# Connectors.net
KiCad netlist of a schematic drawn in Altium Designer
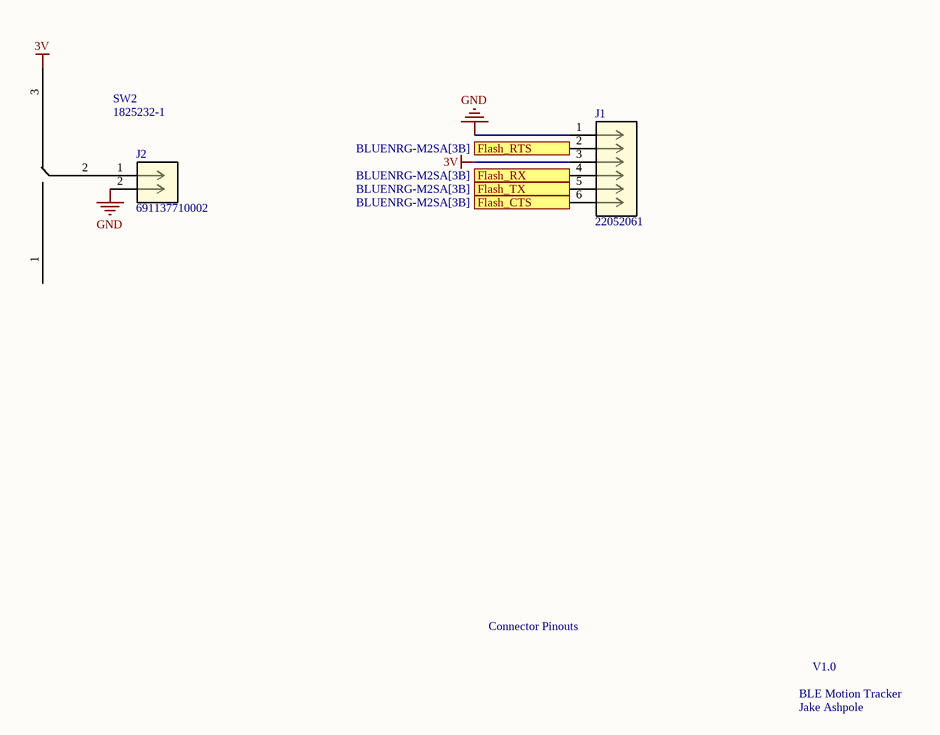
[diagram p0: Connectors.SchDoc]

(export (version "E")
  (design (tool "Eeschema 10.0.6"))
  (components
    (comp (ref "J1")
      (value "22052061")
      (footprint "CONN_22-05-2061_MOL")
      (libsource (lib "22052061") (part "22052061"))
    )
    (comp (ref "J2")
      (value "691137710002")
      (footprint "CONN2_710002_WRE")
      (libsource (lib "691137710002") (part "691137710002"))
    )
    (comp (ref "SW2")
      (value "1825232-1")
      (footprint "1825232-1_TEC")
      (description "https://www.mouser.com/ProductDetail/655-1825232-1")
      (libsource (lib "1825232-1") (part "1825232-1"))
    )
  )
  (nets
    (net (code "1") (name "/Flash_CTS") (class "Default")
      (node (ref "J1") (pin "6") (pinfunction "6_6") (pintype "passive"))
    )
    (net (code "2") (name "/Flash_RTS") (class "Default")
      (node (ref "J1") (pin "2") (pinfunction "2_2") (pintype "passive"))
    )
    (net (code "3") (name "/Flash_RX") (class "Default")
      (node (ref "J1") (pin "4") (pinfunction "4_4") (pintype "passive"))
    )
    (net (code "4") (name "/Flash_TX") (class "Default")
      (node (ref "J1") (pin "5") (pinfunction "5_5") (pintype "passive"))
    )
    (net (code "5") (name "3V") (class "Default")
      (node (ref "J1") (pin "3") (pinfunction "3_3") (pintype "passive"))
      (node (ref "SW2") (pin "3") (pinfunction "3_3") (pintype "passive"))
    )
    (net (code "6") (name "GND") (class "Default")
      (node (ref "J1") (pin "1") (pinfunction "1_1") (pintype "passive"))
      (node (ref "J2") (pin "2") (pinfunction "2_2") (pintype "passive"))
    )
    (net (code "7") (name "Net-(J2-Pad1)") (class "Default")
      (node (ref "J2") (pin "1") (pinfunction "1_1") (pintype "passive"))
      (node (ref "SW2") (pin "2") (pinfunction "2_2") (pintype "passive"))
    )
    (net (code "8") (name "unconnected-(SW2-Pad1)") (class "Default")
      (node (ref "SW2") (pin "1") (pinfunction "1_1") (pintype "passive"))
    )
  )
)
